# ADC3_FPGA.net
KiCad netlist of a schematic drawn in EAGLE
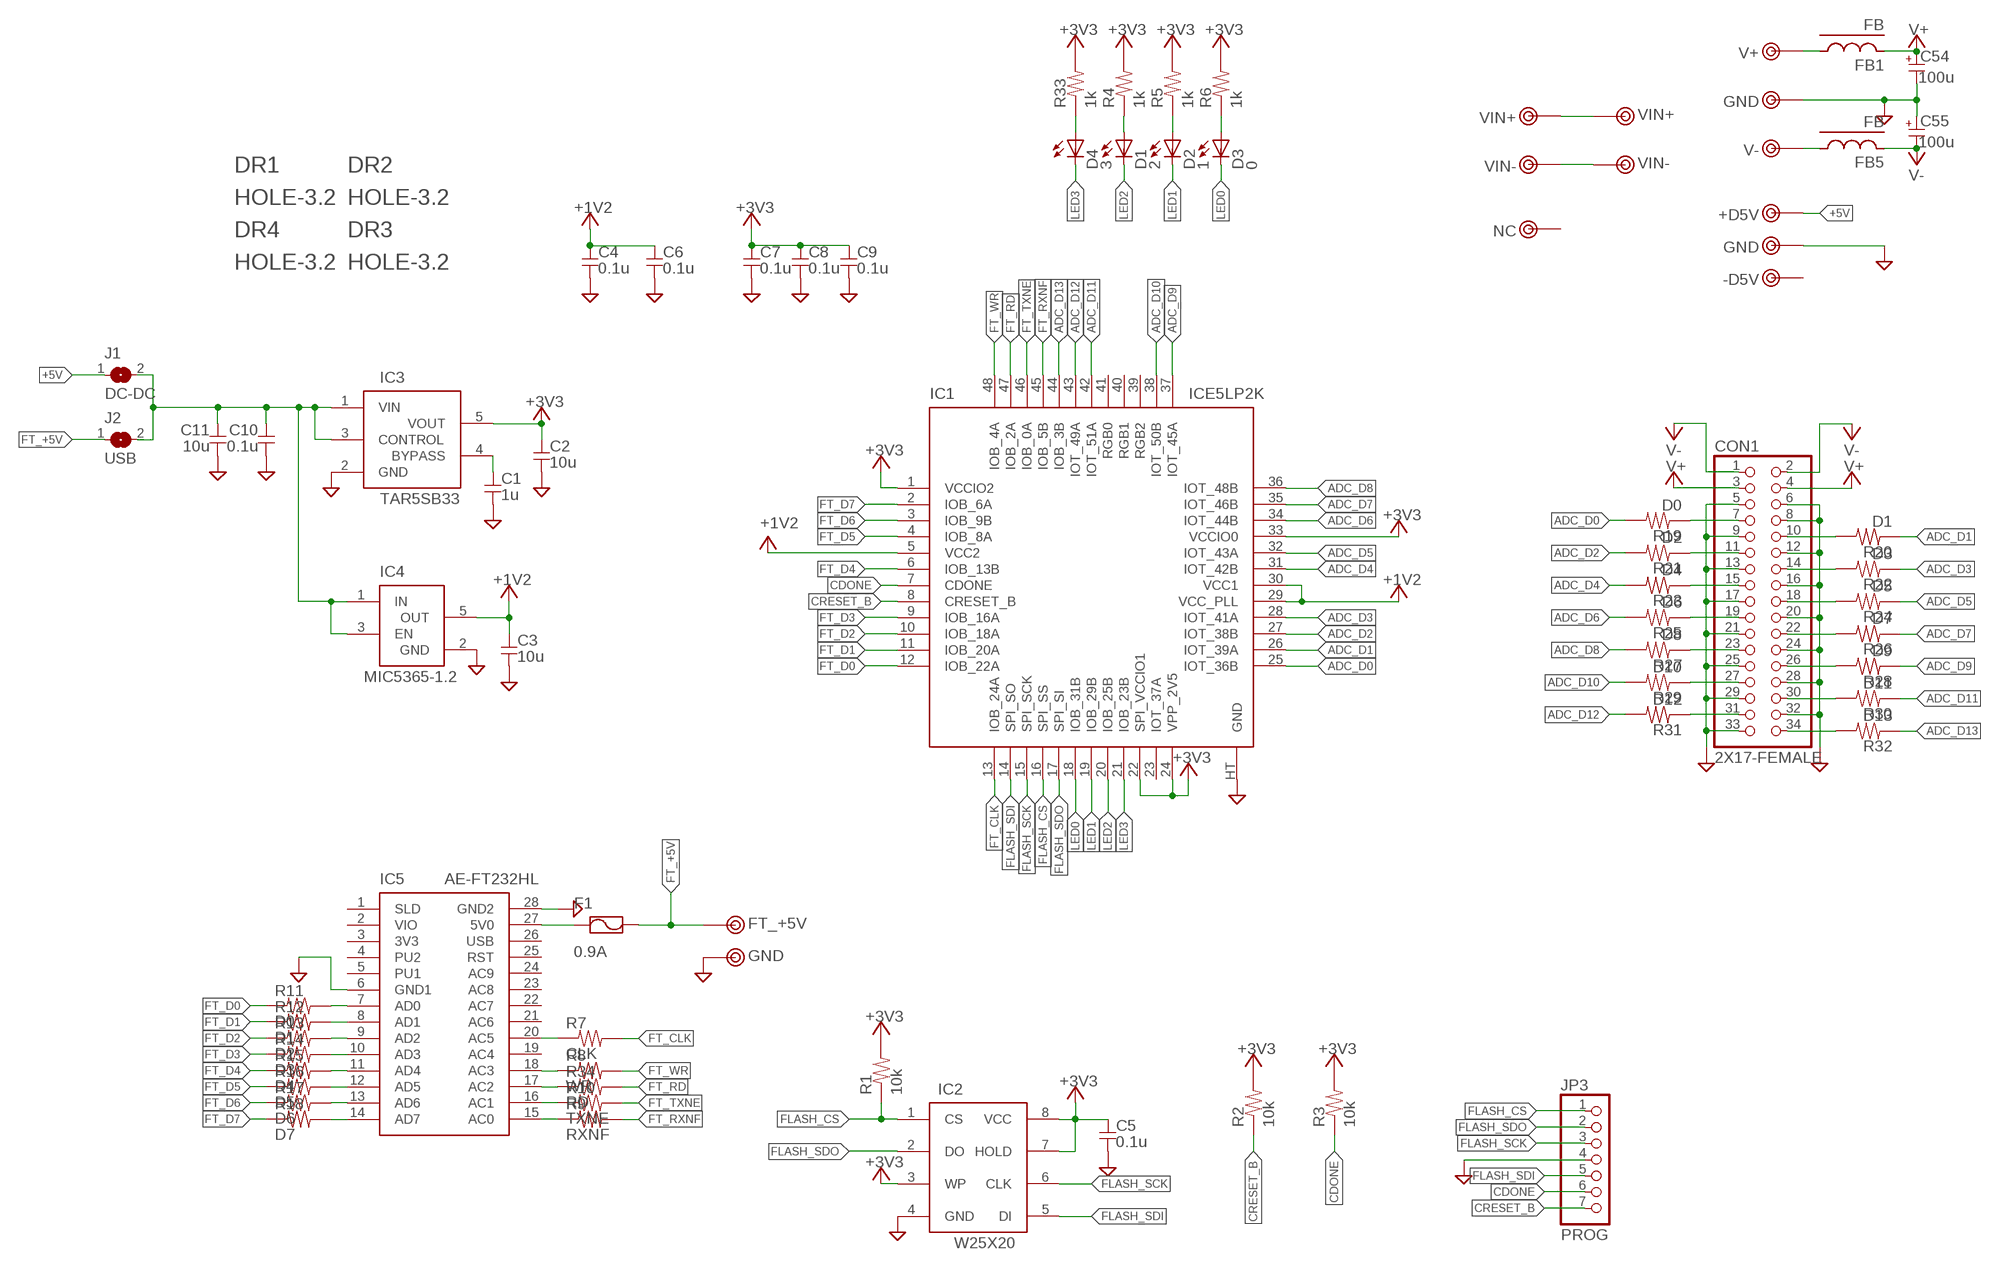
[diagram p0: schematic, sheet 1]

(export (version "E")
  (design (tool "Eeschema 10.0.6"))
  (components
    (comp (ref "C1")
      (value "1u")
      (footprint "eagle-import:1608")
      (libsource (lib "eagle-import") (part "C-1608"))
    )
    (comp (ref "C2")
      (value "10u")
      (footprint "eagle-import:2012")
      (libsource (lib "eagle-import") (part "C-2012"))
    )
    (comp (ref "C3")
      (value "10u")
      (footprint "eagle-import:2012")
      (libsource (lib "eagle-import") (part "C-2012"))
    )
    (comp (ref "C4")
      (value "0.1u")
      (footprint "eagle-import:1608")
      (libsource (lib "eagle-import") (part "C-1608"))
    )
    (comp (ref "C5")
      (value "0.1u")
      (footprint "eagle-import:1608")
      (libsource (lib "eagle-import") (part "C-1608"))
    )
    (comp (ref "C6")
      (value "0.1u")
      (footprint "eagle-import:1608")
      (libsource (lib "eagle-import") (part "C-1608"))
    )
    (comp (ref "C7")
      (value "0.1u")
      (footprint "eagle-import:1608")
      (libsource (lib "eagle-import") (part "C-1608"))
    )
    (comp (ref "C8")
      (value "0.1u")
      (footprint "eagle-import:1608")
      (libsource (lib "eagle-import") (part "C-1608"))
    )
    (comp (ref "C9")
      (value "0.1u")
      (footprint "eagle-import:1608")
      (libsource (lib "eagle-import") (part "C-1608"))
    )
    (comp (ref "C10")
      (value "0.1u")
      (footprint "eagle-import:1608")
      (libsource (lib "eagle-import") (part "C-1608"))
    )
    (comp (ref "C11")
      (value "10u")
      (footprint "eagle-import:3216")
      (libsource (lib "eagle-import") (part "C-3216"))
    )
    (comp (ref "C54")
      (value "100u")
      (footprint "eagle-import:E2,5-8")
      (libsource (lib "eagle-import") (part "CPOLE2.5-8"))
    )
    (comp (ref "C55")
      (value "100u")
      (footprint "eagle-import:E2,5-8")
      (libsource (lib "eagle-import") (part "CPOLE2.5-8"))
    )
    (comp (ref "CON1")
      (value "2X17-FEMALE")
      (footprint "eagle-import:2X17_90")
      (libsource (lib "eagle-import") (part "2X17-FEMALE"))
    )
    (comp (ref "D1")
      (value "2")
      (footprint "eagle-import:D1608")
      (libsource (lib "eagle-import") (part "LED-SMD1608"))
    )
    (comp (ref "D2")
      (value "1")
      (footprint "eagle-import:D1608")
      (libsource (lib "eagle-import") (part "LED-SMD1608"))
    )
    (comp (ref "D3")
      (value "0")
      (footprint "eagle-import:D1608")
      (libsource (lib "eagle-import") (part "LED-SMD1608"))
    )
    (comp (ref "D4")
      (value "3")
      (footprint "eagle-import:D1608")
      (libsource (lib "eagle-import") (part "LED-SMD1608"))
    )
    (comp (ref "DR1")
      (value "HOLE-3.2")
      (footprint "eagle-import:HOLE_3.2")
      (libsource (lib "eagle-import") (part "HOLE-3.2"))
    )
    (comp (ref "DR2")
      (value "HOLE-3.2")
      (footprint "eagle-import:HOLE_3.2")
      (libsource (lib "eagle-import") (part "HOLE-3.2"))
    )
    (comp (ref "DR3")
      (value "HOLE-3.2")
      (footprint "eagle-import:HOLE_3.2")
      (libsource (lib "eagle-import") (part "HOLE-3.2"))
    )
    (comp (ref "DR4")
      (value "HOLE-3.2")
      (footprint "eagle-import:HOLE_3.2")
      (libsource (lib "eagle-import") (part "HOLE-3.2"))
    )
    (comp (ref "F1")
      (value "0.9A")
      (footprint "eagle-import:3216")
      (libsource (lib "eagle-import") (part "FUSE-3216"))
    )
    (comp (ref "FB1")
      (value "FB")
      (footprint "eagle-import:2012-J")
      (libsource (lib "eagle-import") (part "FB-2012"))
    )
    (comp (ref "FB5")
      (value "FB")
      (footprint "eagle-import:2012-J")
      (libsource (lib "eagle-import") (part "FB-2012"))
    )
    (comp (ref "IC1")
      (value "ICE5LP2K")
      (footprint "eagle-import:QFN48HT")
      (libsource (lib "eagle-import") (part "ICE5LP2K"))
    )
    (comp (ref "IC2")
      (value "W25X20")
      (footprint "eagle-import:SOP8")
      (libsource (lib "eagle-import") (part "EEPROM_SPI"))
    )
    (comp (ref "IC3")
      (value "TAR5SB33")
      (footprint "eagle-import:SOT23-5")
      (libsource (lib "eagle-import") (part "TAR5SB33"))
    )
    (comp (ref "IC4")
      (value "MIC5365-1.2")
      (footprint "eagle-import:SC70")
      (libsource (lib "eagle-import") (part "MIC5365"))
    )
    (comp (ref "IC5")
      (value "AE-FT232HL")
      (footprint "eagle-import:AE-FT232HL")
      (libsource (lib "eagle-import") (part "AE-FT232HL"))
    )
    (comp (ref "J1")
      (value "DC-DC")
      (footprint "eagle-import:2012-J")
      (libsource (lib "eagle-import") (part "SJ-2012"))
    )
    (comp (ref "J2")
      (value "USB")
      (footprint "eagle-import:2012-J")
      (libsource (lib "eagle-import") (part "SJ-2012"))
    )
    (comp (ref "JP3")
      (value "PROG")
      (footprint "eagle-import:1X07")
      (libsource (lib "eagle-import") (part "PINHD-1X7"))
    )
    (comp (ref "R1")
      (value "10k")
      (footprint "eagle-import:1608")
      (libsource (lib "eagle-import") (part "R-1608"))
    )
    (comp (ref "R2")
      (value "10k")
      (footprint "eagle-import:1608")
      (libsource (lib "eagle-import") (part "R-1608"))
    )
    (comp (ref "R3")
      (value "10k")
      (footprint "eagle-import:1608")
      (libsource (lib "eagle-import") (part "R-1608"))
    )
    (comp (ref "R4")
      (value "1k")
      (footprint "eagle-import:1608")
      (libsource (lib "eagle-import") (part "R-1608"))
    )
    (comp (ref "R5")
      (value "1k")
      (footprint "eagle-import:1608")
      (libsource (lib "eagle-import") (part "R-1608"))
    )
    (comp (ref "R6")
      (value "1k")
      (footprint "eagle-import:1608")
      (libsource (lib "eagle-import") (part "R-1608"))
    )
    (comp (ref "R7")
      (value "CLK")
      (footprint "eagle-import:1608-J")
      (libsource (lib "eagle-import") (part "R-1608J"))
    )
    (comp (ref "R8")
      (value "WR")
      (footprint "eagle-import:1608-J")
      (libsource (lib "eagle-import") (part "R-1608J"))
    )
    (comp (ref "R9")
      (value "RXNF")
      (footprint "eagle-import:1608-J")
      (libsource (lib "eagle-import") (part "R-1608J"))
    )
    (comp (ref "R10")
      (value "TXNE")
      (footprint "eagle-import:1608-J")
      (libsource (lib "eagle-import") (part "R-1608J"))
    )
    (comp (ref "R11")
      (value "D0")
      (footprint "eagle-import:1608-J")
      (libsource (lib "eagle-import") (part "R-1608J"))
    )
    (comp (ref "R12")
      (value "D1")
      (footprint "eagle-import:1608-J")
      (libsource (lib "eagle-import") (part "R-1608J"))
    )
    (comp (ref "R13")
      (value "D2")
      (footprint "eagle-import:1608-J")
      (libsource (lib "eagle-import") (part "R-1608J"))
    )
    (comp (ref "R14")
      (value "D3")
      (footprint "eagle-import:1608-J")
      (libsource (lib "eagle-import") (part "R-1608J"))
    )
    (comp (ref "R15")
      (value "D4")
      (footprint "eagle-import:1608-J")
      (libsource (lib "eagle-import") (part "R-1608J"))
    )
    (comp (ref "R16")
      (value "D5")
      (footprint "eagle-import:1608-J")
      (libsource (lib "eagle-import") (part "R-1608J"))
    )
    (comp (ref "R17")
      (value "D6")
      (footprint "eagle-import:1608-J")
      (libsource (lib "eagle-import") (part "R-1608J"))
    )
    (comp (ref "R18")
      (value "D7")
      (footprint "eagle-import:1608-J")
      (libsource (lib "eagle-import") (part "R-1608J"))
    )
    (comp (ref "R19")
      (value "D0")
      (footprint "eagle-import:1608-J")
      (libsource (lib "eagle-import") (part "R-1608J"))
    )
    (comp (ref "R20")
      (value "D1")
      (footprint "eagle-import:1608-J")
      (libsource (lib "eagle-import") (part "R-1608J"))
    )
    (comp (ref "R21")
      (value "D2")
      (footprint "eagle-import:1608-J")
      (libsource (lib "eagle-import") (part "R-1608J"))
    )
    (comp (ref "R22")
      (value "D3")
      (footprint "eagle-import:1608-J")
      (libsource (lib "eagle-import") (part "R-1608J"))
    )
    (comp (ref "R23")
      (value "D4")
      (footprint "eagle-import:1608-J")
      (libsource (lib "eagle-import") (part "R-1608J"))
    )
    (comp (ref "R24")
      (value "D5")
      (footprint "eagle-import:1608-J")
      (libsource (lib "eagle-import") (part "R-1608J"))
    )
    (comp (ref "R25")
      (value "D6")
      (footprint "eagle-import:1608-J")
      (libsource (lib "eagle-import") (part "R-1608J"))
    )
    (comp (ref "R26")
      (value "D7")
      (footprint "eagle-import:1608-J")
      (libsource (lib "eagle-import") (part "R-1608J"))
    )
    (comp (ref "R27")
      (value "D8")
      (footprint "eagle-import:1608-J")
      (libsource (lib "eagle-import") (part "R-1608J"))
    )
    (comp (ref "R28")
      (value "D9")
      (footprint "eagle-import:1608-J")
      (libsource (lib "eagle-import") (part "R-1608J"))
    )
    (comp (ref "R29")
      (value "D10")
      (footprint "eagle-import:1608-J")
      (libsource (lib "eagle-import") (part "R-1608J"))
    )
    (comp (ref "R30")
      (value "D11")
      (footprint "eagle-import:1608-J")
      (libsource (lib "eagle-import") (part "R-1608J"))
    )
    (comp (ref "R31")
      (value "D12")
      (footprint "eagle-import:1608-J")
      (libsource (lib "eagle-import") (part "R-1608J"))
    )
    (comp (ref "R32")
      (value "D13")
      (footprint "eagle-import:1608-J")
      (libsource (lib "eagle-import") (part "R-1608J"))
    )
    (comp (ref "R33")
      (value "1k")
      (footprint "eagle-import:1608")
      (libsource (lib "eagle-import") (part "R-1608"))
    )
    (comp (ref "R34")
      (value "RD")
      (footprint "eagle-import:1608-J")
      (libsource (lib "eagle-import") (part "R-1608J"))
    )
    (comp (ref "TP1")
      (value "+D5V")
      (footprint "eagle-import:TESTPIN")
      (libsource (lib "eagle-import") (part "TESTPIN"))
    )
    (comp (ref "TP2")
      (value "NC")
      (footprint "eagle-import:TESTPIN")
      (libsource (lib "eagle-import") (part "TESTPIN"))
    )
    (comp (ref "TP3")
      (value "GND")
      (footprint "eagle-import:TESTPIN")
      (libsource (lib "eagle-import") (part "TESTPIN"))
    )
    (comp (ref "TP4")
      (value "FT_+5V")
      (footprint "eagle-import:TESTPIN")
      (libsource (lib "eagle-import") (part "TESTPIN"))
    )
    (comp (ref "TP5")
      (value "GND")
      (footprint "eagle-import:TESTPIN")
      (libsource (lib "eagle-import") (part "TESTPIN"))
    )
    (comp (ref "TP15")
      (value "-D5V")
      (footprint "eagle-import:TESTPIN")
      (libsource (lib "eagle-import") (part "TESTPIN"))
    )
    (comp (ref "TP17")
      (value "V+")
      (footprint "eagle-import:TESTPIN")
      (libsource (lib "eagle-import") (part "TESTPIN"))
    )
    (comp (ref "TP18")
      (value "GND")
      (footprint "eagle-import:TESTPIN")
      (libsource (lib "eagle-import") (part "TESTPIN"))
    )
    (comp (ref "TP19")
      (value "V-")
      (footprint "eagle-import:TESTPIN")
      (libsource (lib "eagle-import") (part "TESTPIN"))
    )
    (comp (ref "TP21")
      (value "VIN+")
      (footprint "eagle-import:TESTPIN")
      (libsource (lib "eagle-import") (part "TESTPIN"))
    )
    (comp (ref "TP22")
      (value "VIN-")
      (footprint "eagle-import:TESTPIN")
      (libsource (lib "eagle-import") (part "TESTPIN"))
    )
    (comp (ref "TP30")
      (value "VIN+")
      (footprint "eagle-import:TESTPIN")
      (libsource (lib "eagle-import") (part "TESTPIN"))
    )
    (comp (ref "TP31")
      (value "VIN-")
      (footprint "eagle-import:TESTPIN")
      (libsource (lib "eagle-import") (part "TESTPIN"))
    )
  )
  (nets
    (net (code "1") (name "+1V2") (class "Default")
      (node (ref "C3") (pin "1") (pinfunction "1_1") (pintype "passive"))
      (node (ref "C4") (pin "1") (pinfunction "1_1") (pintype "passive"))
      (node (ref "C6") (pin "1") (pinfunction "1_1") (pintype "passive"))
      (node (ref "IC1") (pin "29") (pinfunction "VCC_PLL_29") (pintype "power_in"))
      (node (ref "IC1") (pin "30") (pinfunction "VCC1_30") (pintype "power_in"))
      (node (ref "IC1") (pin "5") (pinfunction "VCC2_5") (pintype "power_in"))
      (node (ref "IC4") (pin "5") (pinfunction "OUT_5") (pintype "power_in"))
    )
    (net (code "2") (name "+3V3") (class "Default")
      (node (ref "C2") (pin "1") (pinfunction "1_1") (pintype "passive"))
      (node (ref "C5") (pin "1") (pinfunction "1_1") (pintype "passive"))
      (node (ref "C7") (pin "1") (pinfunction "1_1") (pintype "passive"))
      (node (ref "C8") (pin "1") (pinfunction "1_1") (pintype "passive"))
      (node (ref "C9") (pin "1") (pinfunction "1_1") (pintype "passive"))
      (node (ref "IC1") (pin "1") (pinfunction "VCCIO2_1") (pintype "power_in"))
      (node (ref "IC1") (pin "22") (pinfunction "SPI_VCCIO1_22") (pintype "power_in"))
      (node (ref "IC1") (pin "24") (pinfunction "VPP_2V5_24") (pintype "power_in"))
      (node (ref "IC1") (pin "33") (pinfunction "VCCIO0_33") (pintype "bidirectional"))
      (node (ref "IC2") (pin "3") (pinfunction "WP_3") (pintype "input"))
      (node (ref "IC2") (pin "7") (pinfunction "HOLD_7") (pintype "input"))
      (node (ref "IC2") (pin "8") (pinfunction "VCC_8") (pintype "power_in"))
      (node (ref "IC3") (pin "5") (pinfunction "VOUT_5") (pintype "power_in"))
      (node (ref "R1") (pin "2") (pinfunction "2_2") (pintype "passive"))
      (node (ref "R2") (pin "2") (pinfunction "2_2") (pintype "passive"))
      (node (ref "R3") (pin "2") (pinfunction "2_2") (pintype "passive"))
      (node (ref "R33") (pin "2") (pinfunction "2_2") (pintype "passive"))
      (node (ref "R4") (pin "2") (pinfunction "2_2") (pintype "passive"))
      (node (ref "R5") (pin "2") (pinfunction "2_2") (pintype "passive"))
      (node (ref "R6") (pin "2") (pinfunction "2_2") (pintype "passive"))
    )
    (net (code "3") (name "+5V") (class "Default")
      (node (ref "J1") (pin "1") (pinfunction "1_1") (pintype "passive"))
      (node (ref "TP1") (pin "1") (pinfunction "1_1") (pintype "passive"))
    )
    (net (code "4") (name "ADC_D0") (class "Default")
      (node (ref "IC1") (pin "25") (pinfunction "IOT_36B_25") (pintype "bidirectional"))
      (node (ref "R19") (pin "2") (pinfunction "2_2") (pintype "passive"))
    )
    (net (code "5") (name "ADC_D1") (class "Default")
      (node (ref "IC1") (pin "26") (pinfunction "IOT_39A_26") (pintype "bidirectional"))
      (node (ref "R20") (pin "1") (pinfunction "1_1") (pintype "passive"))
    )
    (net (code "6") (name "ADC_D2") (class "Default")
      (node (ref "IC1") (pin "27") (pinfunction "IOT_38B_27") (pintype "bidirectional"))
      (node (ref "R21") (pin "2") (pinfunction "2_2") (pintype "passive"))
    )
    (net (code "7") (name "ADC_D3") (class "Default")
      (node (ref "IC1") (pin "28") (pinfunction "IOT_41A_28") (pintype "bidirectional"))
      (node (ref "R22") (pin "1") (pinfunction "1_1") (pintype "passive"))
    )
    (net (code "8") (name "ADC_D4") (class "Default")
      (node (ref "IC1") (pin "31") (pinfunction "IOT_42B_31") (pintype "bidirectional"))
      (node (ref "R23") (pin "2") (pinfunction "2_2") (pintype "passive"))
    )
    (net (code "9") (name "ADC_D5") (class "Default")
      (node (ref "IC1") (pin "32") (pinfunction "IOT_43A_32") (pintype "bidirectional"))
      (node (ref "R24") (pin "1") (pinfunction "1_1") (pintype "passive"))
    )
    (net (code "10") (name "ADC_D6") (class "Default")
      (node (ref "IC1") (pin "34") (pinfunction "IOT_44B_34") (pintype "bidirectional"))
      (node (ref "R25") (pin "2") (pinfunction "2_2") (pintype "passive"))
    )
    (net (code "11") (name "ADC_D7") (class "Default")
      (node (ref "IC1") (pin "35") (pinfunction "IOT_46B_35") (pintype "bidirectional"))
      (node (ref "R26") (pin "1") (pinfunction "1_1") (pintype "passive"))
    )
    (net (code "12") (name "ADC_D8") (class "Default")
      (node (ref "IC1") (pin "36") (pinfunction "IOT_48B_36") (pintype "bidirectional"))
      (node (ref "R27") (pin "2") (pinfunction "2_2") (pintype "passive"))
    )
    (net (code "13") (name "ADC_D9") (class "Default")
      (node (ref "IC1") (pin "37") (pinfunction "IOT_45A_37") (pintype "bidirectional"))
      (node (ref "R28") (pin "1") (pinfunction "1_1") (pintype "passive"))
    )
    (net (code "14") (name "ADC_D10") (class "Default")
      (node (ref "IC1") (pin "38") (pinfunction "IOT_50B_38") (pintype "bidirectional"))
      (node (ref "R29") (pin "2") (pinfunction "2_2") (pintype "passive"))
    )
    (net (code "15") (name "ADC_D11") (class "Default")
      (node (ref "IC1") (pin "42") (pinfunction "IOT_51A_42") (pintype "bidirectional"))
      (node (ref "R30") (pin "1") (pinfunction "1_1") (pintype "passive"))
    )
    (net (code "16") (name "ADC_D12") (class "Default")
      (node (ref "IC1") (pin "43") (pinfunction "IOT_49A_43") (pintype "bidirectional"))
      (node (ref "R31") (pin "2") (pinfunction "2_2") (pintype "passive"))
    )
    (net (code "17") (name "ADC_D13") (class "Default")
      (node (ref "IC1") (pin "44") (pinfunction "IOB_3B_44") (pintype "bidirectional"))
      (node (ref "R32") (pin "1") (pinfunction "1_1") (pintype "passive"))
    )
    (net (code "18") (name "CDONE") (class "Default")
      (node (ref "IC1") (pin "7") (pinfunction "CDONE_7") (pintype "bidirectional"))
      (node (ref "JP3") (pin "6") (pinfunction "6_6") (pintype "passive"))
      (node (ref "R3") (pin "1") (pinfunction "1_1") (pintype "passive"))
    )
    (net (code "19") (name "CRESET_B") (class "Default")
      (node (ref "IC1") (pin "8") (pinfunction "CRESET_B_8") (pintype "input"))
      (node (ref "JP3") (pin "7") (pinfunction "7_7") (pintype "passive"))
      (node (ref "R2") (pin "1") (pinfunction "1_1") (pintype "passive"))
    )
    (net (code "20") (name "FLASH_CS") (class "Default")
      (node (ref "IC1") (pin "16") (pinfunction "SPI_SS_16") (pintype "bidirectional"))
      (node (ref "IC2") (pin "1") (pinfunction "CS_1") (pintype "input"))
      (node (ref "JP3") (pin "1") (pinfunction "1_1") (pintype "passive"))
      (node (ref "R1") (pin "1") (pinfunction "1_1") (pintype "passive"))
    )
    (net (code "21") (name "FLASH_SCK") (class "Default")
      (node (ref "IC1") (pin "15") (pinfunction "SPI_SCK_15") (pintype "bidirectional"))
      (node (ref "IC2") (pin "6") (pinfunction "CLK_6") (pintype "input"))
      (node (ref "JP3") (pin "3") (pinfunction "3_3") (pintype "passive"))
    )
    (net (code "22") (name "FLASH_SDI") (class "Default")
      (node (ref "IC1") (pin "14") (pinfunction "SPI_SO_14") (pintype "bidirectional"))
      (node (ref "IC2") (pin "5") (pinfunction "DI_5") (pintype "input"))
      (node (ref "JP3") (pin "5") (pinfunction "5_5") (pintype "passive"))
    )
    (net (code "23") (name "FLASH_SDO") (class "Default")
      (node (ref "IC1") (pin "17") (pinfunction "SPI_SI_17") (pintype "bidirectional"))
      (node (ref "IC2") (pin "2") (pinfunction "DO_2") (pintype "output"))
      (node (ref "JP3") (pin "2") (pinfunction "2_2") (pintype "passive"))
    )
    (net (code "24") (name "FT_+5V") (class "Default")
      (node (ref "F1") (pin "2") (pinfunction "P$2_2") (pintype "passive"))
      (node (ref "J2") (pin "1") (pinfunction "1_1") (pintype "passive"))
      (node (ref "TP4") (pin "1") (pinfunction "1_1") (pintype "passive"))
    )
    (net (code "25") (name "FT_CLK") (class "Default")
      (node (ref "IC1") (pin "13") (pinfunction "IOB_24A_13") (pintype "bidirectional"))
      (node (ref "R7") (pin "2") (pinfunction "2_2") (pintype "passive"))
    )
    (net (code "26") (name "FT_D0") (class "Default")
      (node (ref "IC1") (pin "12") (pinfunction "IOB_22A_12") (pintype "bidirectional"))
      (node (ref "R11") (pin "1") (pinfunction "1_1") (pintype "passive"))
    )
    (net (code "27") (name "FT_D1") (class "Default")
      (node (ref "IC1") (pin "11") (pinfunction "IOB_20A_11") (pintype "bidirectional"))
      (node (ref "R12") (pin "1") (pinfunction "1_1") (pintype "passive"))
    )
    (net (code "28") (name "FT_D2") (class "Default")
      (node (ref "IC1") (pin "10") (pinfunction "IOB_18A_10") (pintype "bidirectional"))
      (node (ref "R13") (pin "1") (pinfunction "1_1") (pintype "passive"))
    )
    (net (code "29") (name "FT_D3") (class "Default")
      (node (ref "IC1") (pin "9") (pinfunction "IOB_16A_9") (pintype "bidirectional"))
      (node (ref "R14") (pin "1") (pinfunction "1_1") (pintype "passive"))
    )
    (net (code "30") (name "FT_D4") (class "Default")
      (node (ref "IC1") (pin "6") (pinfunction "IOB_13B_6") (pintype "bidirectional"))
      (node (ref "R15") (pin "1") (pinfunction "1_1") (pintype "passive"))
    )
    (net (code "31") (name "FT_D5") (class "Default")
      (node (ref "IC1") (pin "4") (pinfunction "IOB_8A_4") (pintype "bidirectional"))
      (node (ref "R16") (pin "1") (pinfunction "1_1") (pintype "passive"))
    )
    (net (code "32") (name "FT_D6") (class "Default")
      (node (ref "IC1") (pin "3") (pinfunction "IOB_9B_3") (pintype "bidirectional"))
      (node (ref "R17") (pin "1") (pinfunction "1_1") (pintype "passive"))
    )
    (net (code "33") (name "FT_D7") (class "Default")
      (node (ref "IC1") (pin "2") (pinfunction "IOB_6A_2") (pintype "bidirectional"))
      (node (ref "R18") (pin "1") (pinfunction "1_1") (pintype "passive"))
    )
    (net (code "34") (name "FT_RD") (class "Default")
      (node (ref "IC1") (pin "47") (pinfunction "IOB_2A_47") (pintype "bidirectional"))
      (node (ref "R34") (pin "2") (pinfunction "2_2") (pintype "passive"))
    )
    (net (code "35") (name "FT_RXNF") (class "Default")
      (node (ref "IC1") (pin "45") (pinfunction "IOB_5B_45") (pintype "bidirectional"))
      (node (ref "R9") (pin "2") (pinfunction "2_2") (pintype "passive"))
    )
    (net (code "36") (name "FT_TXNE") (class "Default")
      (node (ref "IC1") (pin "46") (pinfunction "IOB_0A_46") (pintype "bidirectional"))
      (node (ref "R10") (pin "2") (pinfunction "2_2") (pintype "passive"))
    )
    (net (code "37") (name "FT_WR") (class "Default")
      (node (ref "IC1") (pin "48") (pinfunction "IOB_4A_48") (pintype "bidirectional"))
      (node (ref "R8") (pin "2") (pinfunction "2_2") (pintype "passive"))
    )
    (net (code "38") (name "GND") (class "Default")
      (node (ref "C1") (pin "2") (pinfunction "2_2") (pintype "passive"))
      (node (ref "C10") (pin "2") (pinfunction "2_2") (pintype "passive"))
      (node (ref "C11") (pin "2") (pinfunction "2_2") (pintype "passive"))
      (node (ref "C2") (pin "2") (pinfunction "2_2") (pintype "passive"))
      (node (ref "C3") (pin "2") (pinfunction "2_2") (pintype "passive"))
      (node (ref "C4") (pin "2") (pinfunction "2_2") (pintype "passive"))
      (node (ref "C5") (pin "2") (pinfunction "2_2") (pintype "passive"))
      (node (ref "C54") (pin "-") (pinfunction "2_-") (pintype "passive"))
      (node (ref "C55") (pin "+") (pinfunction "1_+") (pintype "passive"))
      (node (ref "C6") (pin "2") (pinfunction "2_2") (pintype "passive"))
      (node (ref "C7") (pin "2") (pinfunction "2_2") (pintype "passive"))
      (node (ref "C8") (pin "2") (pinfunction "2_2") (pintype "passive"))
      (node (ref "C9") (pin "2") (pinfunction "2_2") (pintype "passive"))
      (node (ref "CON1") (pin "12") (pinfunction "12_12") (pintype "passive"))
      (node (ref "CON1") (pin "13") (pinfunction "13_13") (pintype "passive"))
      (node (ref "CON1") (pin "16") (pinfunction "16_16") (pintype "passive"))
      (node (ref "CON1") (pin "17") (pinfunction "17_17") (pintype "passive"))
      (node (ref "CON1") (pin "20") (pinfunction "20_20") (pintype "passive"))
      (node (ref "CON1") (pin "21") (pinfunction "21_21") (pintype "passive"))
      (node (ref "CON1") (pin "24") (pinfunction "24_24") (pintype "passive"))
      (node (ref "CON1") (pin "25") (pinfunction "25_25") (pintype "passive"))
      (node (ref "CON1") (pin "28") (pinfunction "28_28") (pintype "passive"))
      (node (ref "CON1") (pin "29") (pinfunction "29_29") (pintype "passive"))
      (node (ref "CON1") (pin "32") (pinfunction "32_32") (pintype "passive"))
      (node (ref "CON1") (pin "33") (pinfunction "33_33") (pintype "passive"))
      (node (ref "CON1") (pin "5") (pinfunction "5_5") (pintype "passive"))
      (node (ref "CON1") (pin "6") (pinfunction "6_6") (pintype "passive"))
      (node (ref "CON1") (pin "8") (pinfunction "8_8") (pintype "passive"))
      (node (ref "CON1") (pin "9") (pinfunction "9_9") (pintype "passive"))
      (node (ref "IC1") (pin "HT") (pinfunction "GND_HT") (pintype "power_in"))
      (node (ref "IC2") (pin "4") (pinfunction "GND_4") (pintype "power_in"))
      (node (ref "IC3") (pin "2") (pinfunction "GND_2") (pintype "power_in"))
      (node (ref "IC4") (pin "2") (pinfunction "GND_2") (pintype "power_in"))
      (node (ref "IC5") (pin "28") (pinfunction "GND2_28") (pintype "power_in"))
      (node (ref "IC5") (pin "6") (pinfunction "GND1_6") (pintype "power_in"))
      (node (ref "JP3") (pin "4") (pinfunction "4_4") (pintype "passive"))
      (node (ref "TP18") (pin "1") (pinfunction "1_1") (pintype "passive"))
      (node (ref "TP3") (pin "1") (pinfunction "1_1") (pintype "passive"))
      (node (ref "TP5") (pin "1") (pinfunction "1_1") (pintype "passive"))
    )
    (net (code "39") (name "LED0") (class "Default")
      (node (ref "D3") (pin "K") (pinfunction "K_K") (pintype "passive"))
      (node (ref "IC1") (pin "18") (pinfunction "IOB_31B_18") (pintype "bidirectional"))
    )
    (net (code "40") (name "LED1") (class "Default")
      (node (ref "D2") (pin "K") (pinfunction "K_K") (pintype "passive"))
      (node (ref "IC1") (pin "19") (pinfunction "IOB_29B_19") (pintype "bidirectional"))
    )
    (net (code "41") (name "LED2") (class "Default")
      (node (ref "D1") (pin "K") (pinfunction "K_K") (pintype "passive"))
      (node (ref "IC1") (pin "20") (pinfunction "IOB_25B_20") (pintype "bidirectional"))
    )
    (net (code "42") (name "LED3") (class "Default")
      (node (ref "D4") (pin "K") (pinfunction "K_K") (pintype "passive"))
      (node (ref "IC1") (pin "21") (pinfunction "IOB_23B_21") (pintype "bidirectional"))
    )
    (net (code "43") (name "Net-(CON1-Pad7)") (class "Default")
      (node (ref "CON1") (pin "7") (pinfunction "7_7") (pintype "passive"))
      (node (ref "R19") (pin "1") (pinfunction "1_1") (pintype "passive"))
    )
    (net (code "44") (name "Net-(CON1-Pad10)") (class "Default")
      (node (ref "CON1") (pin "10") (pinfunction "10_10") (pintype "passive"))
      (node (ref "R20") (pin "2") (pinfunction "2_2") (pintype "passive"))
    )
    (net (code "45") (name "Net-(CON1-Pad11)") (class "Default")
      (node (ref "CON1") (pin "11") (pinfunction "11_11") (pintype "passive"))
      (node (ref "R21") (pin "1") (pinfunction "1_1") (pintype "passive"))
    )
    (net (code "46") (name "Net-(CON1-Pad14)") (class "Default")
      (node (ref "CON1") (pin "14") (pinfunction "14_14") (pintype "passive"))
      (node (ref "R22") (pin "2") (pinfunction "2_2") (pintype "passive"))
    )
    (net (code "47") (name "Net-(CON1-Pad15)") (class "Default")
      (node (ref "CON1") (pin "15") (pinfunction "15_15") (pintype "passive"))
      (node (ref "R23") (pin "1") (pinfunction "1_1") (pintype "passive"))
    )
    (net (code "48") (name "Net-(CON1-Pad18)") (class "Default")
      (node (ref "CON1") (pin "18") (pinfunction "18_18") (pintype "passive"))
      (node (ref "R24") (pin "2") (pinfunction "2_2") (pintype "passive"))
    )
    (net (code "49") (name "Net-(CON1-Pad19)") (class "Default")
      (node (ref "CON1") (pin "19") (pinfunction "19_19") (pintype "passive"))
      (node (ref "R25") (pin "1") (pinfunction "1_1") (pintype "passive"))
    )
    (net (code "50") (name "Net-(CON1-Pad22)") (class "Default")
      (node (ref "CON1") (pin "22") (pinfunction "22_22") (pintype "passive"))
      (node (ref "R26") (pin "2") (pinfunction "2_2") (pintype "passive"))
    )
    (net (code "51") (name "Net-(CON1-Pad23)") (class "Default")
      (node (ref "CON1") (pin "23") (pinfunction "23_23") (pintype "passive"))
      (node (ref "R27") (pin "1") (pinfunction "1_1") (pintype "passive"))
    )
    (net (code "52") (name "Net-(CON1-Pad26)") (class "Default")
      (node (ref "CON1") (pin "26") (pinfunction "26_26") (pintype "passive"))
      (node (ref "R28") (pin "2") (pinfunction "2_2") (pintype "passive"))
    )
    (net (code "53") (name "Net-(CON1-Pad27)") (class "Default")
      (node (ref "CON1") (pin "27") (pinfunction "27_27") (pintype "passive"))
      (node (ref "R29") (pin "1") (pinfunction "1_1") (pintype "passive"))
    )
    (net (code "54") (name "Net-(CON1-Pad30)") (class "Default")
      (node (ref "CON1") (pin "30") (pinfunction "30_30") (pintype "passive"))
      (node (ref "R30") (pin "2") (pinfunction "2_2") (pintype "passive"))
    )
    (net (code "55") (name "Net-(CON1-Pad31)") (class "Default")
      (node (ref "CON1") (pin "31") (pinfunction "31_31") (pintype "passive"))
      (node (ref "R31") (pin "1") (pinfunction "1_1") (pintype "passive"))
    )
    (net (code "56") (name "Net-(CON1-Pad34)") (class "Default")
      (node (ref "CON1") (pin "34") (pinfunction "34_34") (pintype "passive"))
      (node (ref "R32") (pin "2") (pinfunction "2_2") (pintype "passive"))
    )
    (net (code "57") (name "Net-(D1-PadA)") (class "Default")
      (node (ref "D1") (pin "A") (pinfunction "A_A") (pintype "passive"))
      (node (ref "R4") (pin "1") (pinfunction "1_1") (pintype "passive"))
    )
    (net (code "58") (name "Net-(D2-PadA)") (class "Default")
      (node (ref "D2") (pin "A") (pinfunction "A_A") (pintype "passive"))
      (node (ref "R5") (pin "1") (pinfunction "1_1") (pintype "passive"))
    )
    (net (code "59") (name "Net-(D3-PadA)") (class "Default")
      (node (ref "D3") (pin "A") (pinfunction "A_A") (pintype "passive"))
      (node (ref "R6") (pin "1") (pinfunction "1_1") (pintype "passive"))
    )
    (net (code "60") (name "Net-(D4-PadA)") (class "Default")
      (node (ref "D4") (pin "A") (pinfunction "A_A") (pintype "passive"))
      (node (ref "R33") (pin "1") (pinfunction "1_1") (pintype "passive"))
    )
    (net (code "61") (name "Net-(F1-P$1)") (class "Default")
      (node (ref "F1") (pin "1") (pinfunction "P$1_1") (pintype "passive"))
      (node (ref "IC5") (pin "27") (pinfunction "5V0_27") (pintype "output"))
    )
    (net (code "62") (name "Net-(FB1-Pad1)") (class "Default")
      (node (ref "FB1") (pin "1") (pinfunction "1_1") (pintype "passive"))
      (node (ref "TP17") (pin "1") (pinfunction "1_1") (pintype "passive"))
    )
    (net (code "63") (name "Net-(FB5-Pad1)") (class "Default")
      (node (ref "FB5") (pin "1") (pinfunction "1_1") (pintype "passive"))
      (node (ref "TP19") (pin "1") (pinfunction "1_1") (pintype "passive"))
    )
    (net (code "64") (name "Net-(IC3-BYPASS)") (class "Default")
      (node (ref "C1") (pin "1") (pinfunction "1_1") (pintype "passive"))
      (node (ref "IC3") (pin "4") (pinfunction "BYPASS_4") (pintype "passive"))
    )
    (net (code "65") (name "Net-(IC3-CONTROL)") (class "Default")
      (node (ref "C10") (pin "1") (pinfunction "1_1") (pintype "passive"))
      (node (ref "C11") (pin "1") (pinfunction "1_1") (pintype "passive"))
      (node (ref "IC3") (pin "1") (pinfunction "VIN_1") (pintype "power_in"))
      (node (ref "IC3") (pin "3") (pinfunction "CONTROL_3") (pintype "input"))
      (node (ref "IC4") (pin "1") (pinfunction "IN_1") (pintype "power_in"))
      (node (ref "IC4") (pin "3") (pinfunction "EN_3") (pintype "input"))
      (node (ref "J1") (pin "2") (pinfunction "2_2") (pintype "passive"))
      (node (ref "J2") (pin "2") (pinfunction "2_2") (pintype "passive"))
    )
    (net (code "66") (name "Net-(IC5-AC0)") (class "Default")
      (node (ref "IC5") (pin "15") (pinfunction "AC0_15") (pintype "bidirectional"))
      (node (ref "R9") (pin "1") (pinfunction "1_1") (pintype "passive"))
    )
    (net (code "67") (name "Net-(IC5-AC1)") (class "Default")
      (node (ref "IC5") (pin "16") (pinfunction "AC1_16") (pintype "bidirectional"))
      (node (ref "R10") (pin "1") (pinfunction "1_1") (pintype "passive"))
    )
    (net (code "68") (name "Net-(IC5-AC2)") (class "Default")
      (node (ref "IC5") (pin "17") (pinfunction "AC2_17") (pintype "bidirectional"))
      (node (ref "R34") (pin "1") (pinfunction "1_1") (pintype "passive"))
    )
    (net (code "69") (name "Net-(IC5-AC3)") (class "Default")
      (node (ref "IC5") (pin "18") (pinfunction "AC3_18") (pintype "bidirectional"))
      (node (ref "R8") (pin "1") (pinfunction "1_1") (pintype "passive"))
    )
    (net (code "70") (name "Net-(IC5-AC5)") (class "Default")
      (node (ref "IC5") (pin "20") (pinfunction "AC5_20") (pintype "bidirectional"))
      (node (ref "R7") (pin "1") (pinfunction "1_1") (pintype "passive"))
    )
    (net (code "71") (name "Net-(IC5-AD0)") (class "Default")
      (node (ref "IC5") (pin "7") (pinfunction "AD0_7") (pintype "bidirectional"))
      (node (ref "R11") (pin "2") (pinfunction "2_2") (pintype "passive"))
    )
    (net (code "72") (name "Net-(IC5-AD1)") (class "Default")
      (node (ref "IC5") (pin "8") (pinfunction "AD1_8") (pintype "bidirectional"))
      (node (ref "R12") (pin "2") (pinfunction "2_2") (pintype "passive"))
    )
    (net (code "73") (name "Net-(IC5-AD2)") (class "Default")
      (node (ref "IC5") (pin "9") (pinfunction "AD2_9") (pintype "bidirectional"))
      (node (ref "R13") (pin "2") (pinfunction "2_2") (pintype "passive"))
    )
    (net (code "74") (name "Net-(IC5-AD3)") (class "Default")
      (node (ref "IC5") (pin "10") (pinfunction "AD3_10") (pintype "bidirectional"))
      (node (ref "R14") (pin "2") (pinfunction "2_2") (pintype "passive"))
    )
    (net (code "75") (name "Net-(IC5-AD4)") (class "Default")
      (node (ref "IC5") (pin "11") (pinfunction "AD4_11") (pintype "bidirectional"))
      (node (ref "R15") (pin "2") (pinfunction "2_2") (pintype "passive"))
    )
    (net (code "76") (name "Net-(IC5-AD5)") (class "Default")
      (node (ref "IC5") (pin "12") (pinfunction "AD5_12") (pintype "bidirectional"))
      (node (ref "R16") (pin "2") (pinfunction "2_2") (pintype "passive"))
    )
    (net (code "77") (name "Net-(IC5-AD6)") (class "Default")
      (node (ref "IC5") (pin "13") (pinfunction "AD6_13") (pintype "bidirectional"))
      (node (ref "R17") (pin "2") (pinfunction "2_2") (pintype "passive"))
    )
    (net (code "78") (name "Net-(IC5-AD7)") (class "Default")
      (node (ref "IC5") (pin "14") (pinfunction "AD7_14") (pintype "bidirectional"))
      (node (ref "R18") (pin "2") (pinfunction "2_2") (pintype "passive"))
    )
    (net (code "79") (name "Net-(TP21-Pad1)") (class "Default")
      (node (ref "TP21") (pin "1") (pinfunction "1_1") (pintype "passive"))
      (node (ref "TP30") (pin "1") (pinfunction "1_1") (pintype "passive"))
    )
    (net (code "80") (name "Net-(TP22-Pad1)") (class "Default")
      (node (ref "TP22") (pin "1") (pinfunction "1_1") (pintype "passive"))
      (node (ref "TP31") (pin "1") (pinfunction "1_1") (pintype "passive"))
    )
    (net (code "81") (name "V+") (class "Default")
      (node (ref "C54") (pin "+") (pinfunction "1_+") (pintype "passive"))
      (node (ref "CON1") (pin "3") (pinfunction "3_3") (pintype "passive"))
      (node (ref "CON1") (pin "4") (pinfunction "4_4") (pintype "passive"))
      (node (ref "FB1") (pin "2") (pinfunction "2_2") (pintype "passive"))
    )
    (net (code "82") (name "V-") (class "Default")
      (node (ref "C55") (pin "-") (pinfunction "2_-") (pintype "passive"))
      (node (ref "CON1") (pin "1") (pinfunction "1_1") (pintype "passive"))
      (node (ref "CON1") (pin "2") (pinfunction "2_2") (pintype "passive"))
      (node (ref "FB5") (pin "2") (pinfunction "2_2") (pintype "passive"))
    )
    (net (code "83") (name "unconnected-(IC1-IOT_37A-Pad23)") (class "Default")
      (node (ref "IC1") (pin "23") (pinfunction "IOT_37A_23") (pintype "bidirectional"))
    )
    (net (code "84") (name "unconnected-(IC1-RGB0-Pad41)") (class "Default")
      (node (ref "IC1") (pin "41") (pinfunction "RGB0_41") (pintype "bidirectional"))
    )
    (net (code "85") (name "unconnected-(IC1-RGB1-Pad40)") (class "Default")
      (node (ref "IC1") (pin "40") (pinfunction "RGB1_40") (pintype "bidirectional"))
    )
    (net (code "86") (name "unconnected-(IC1-RGB2-Pad39)") (class "Default")
      (node (ref "IC1") (pin "39") (pinfunction "RGB2_39") (pintype "bidirectional"))
    )
    (net (code "87") (name "unconnected-(IC5-3V3-Pad3)") (class "Default")
      (node (ref "IC5") (pin "3") (pinfunction "3V3_3") (pintype "output"))
    )
    (net (code "88") (name "unconnected-(IC5-AC4-Pad19)") (class "Default")
      (node (ref "IC5") (pin "19") (pinfunction "AC4_19") (pintype "bidirectional"))
    )
    (net (code "89") (name "unconnected-(IC5-AC6-Pad21)") (class "Default")
      (node (ref "IC5") (pin "21") (pinfunction "AC6_21") (pintype "bidirectional"))
    )
    (net (code "90") (name "unconnected-(IC5-AC7-Pad22)") (class "Default")
      (node (ref "IC5") (pin "22") (pinfunction "AC7_22") (pintype "bidirectional"))
    )
    (net (code "91") (name "unconnected-(IC5-AC8-Pad23)") (class "Default")
      (node (ref "IC5") (pin "23") (pinfunction "AC8_23") (pintype "bidirectional"))
    )
    (net (code "92") (name "unconnected-(IC5-AC9-Pad24)") (class "Default")
      (node (ref "IC5") (pin "24") (pinfunction "AC9_24") (pintype "bidirectional"))
    )
    (net (code "93") (name "unconnected-(IC5-PU1-Pad5)") (class "Default")
      (node (ref "IC5") (pin "5") (pinfunction "PU1_5") (pintype "bidirectional"))
    )
    (net (code "94") (name "unconnected-(IC5-PU2-Pad4)") (class "Default")
      (node (ref "IC5") (pin "4") (pinfunction "PU2_4") (pintype "bidirectional"))
    )
    (net (code "95") (name "unconnected-(IC5-RST-Pad25)") (class "Default")
      (node (ref "IC5") (pin "25") (pinfunction "RST_25") (pintype "bidirectional"))
    )
    (net (code "96") (name "unconnected-(IC5-SLD-Pad1)") (class "Default")
      (node (ref "IC5") (pin "1") (pinfunction "SLD_1") (pintype "bidirectional"))
    )
    (net (code "97") (name "unconnected-(IC5-USB-Pad26)") (class "Default")
      (node (ref "IC5") (pin "26") (pinfunction "USB_26") (pintype "bidirectional"))
    )
    (net (code "98") (name "unconnected-(IC5-VIO-Pad2)") (class "Default")
      (node (ref "IC5") (pin "2") (pinfunction "VIO_2") (pintype "output"))
    )
    (net (code "99") (name "unconnected-(TP2-Pad1)") (class "Default")
      (node (ref "TP2") (pin "1") (pinfunction "1_1") (pintype "passive"))
    )
    (net (code "100") (name "unconnected-(TP15-Pad1)") (class "Default")
      (node (ref "TP15") (pin "1") (pinfunction "1_1") (pintype "passive"))
    )
  )
)
